# sensorbridge.net
KiCad netlist of a schematic drawn in EAGLE
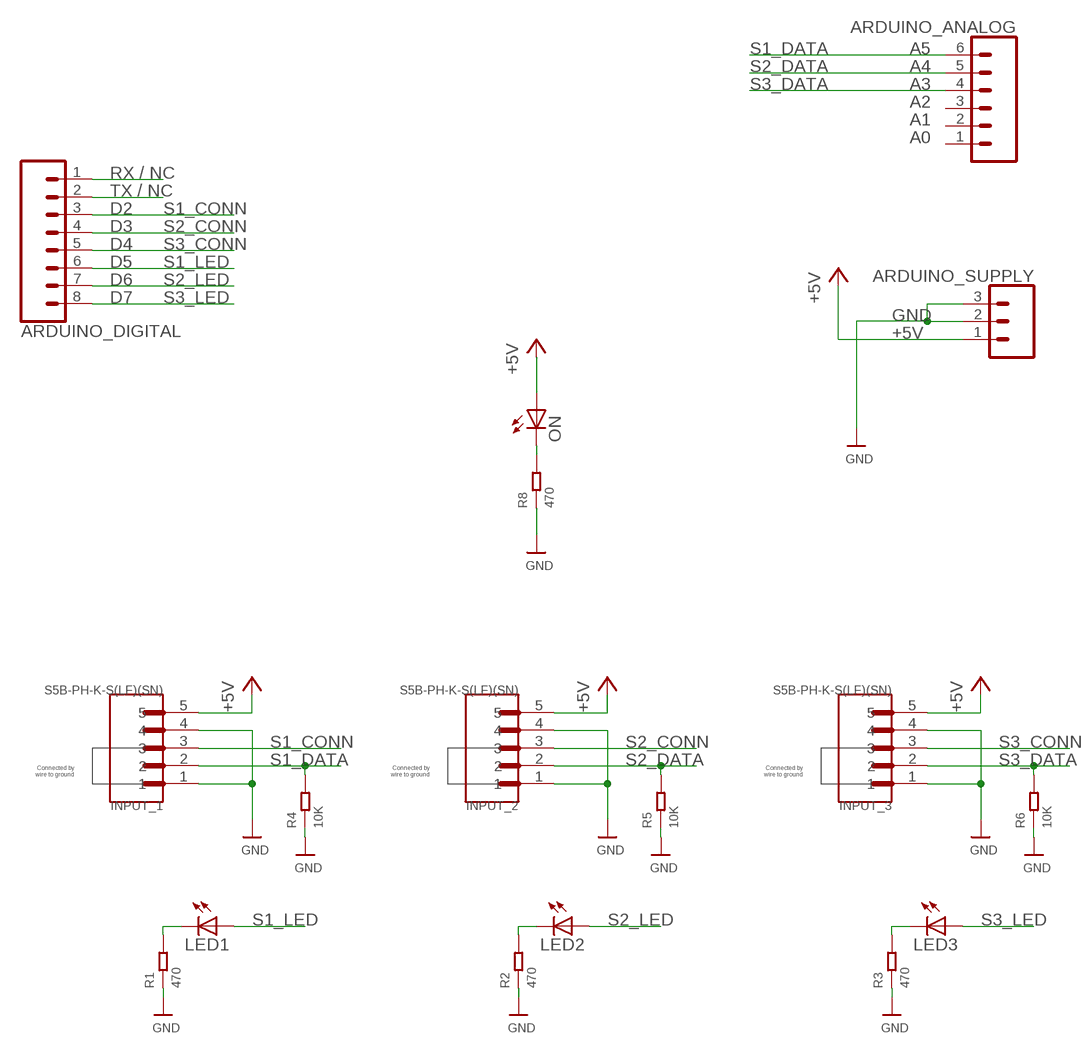
[diagram p0: schematic, sheet 1]

(export (version "E")
  (design (tool "Eeschema 10.0.6"))
  (components
    (comp (ref "ARDUINO_ANALOG")
      (value "CONN_06NO_SILK_FEMALE_PTH")
      (footprint "eagle-import:1X06_NO_SILK")
      (libsource (lib "eagle-import") (part "CONN_06NO_SILK_FEMALE_PTH"))
    )
    (comp (ref "ARDUINO_DIGITAL")
      (value "CONN_08NO_SILK_FEMALE_PTH")
      (footprint "eagle-import:1X08_NO_SILK")
      (libsource (lib "eagle-import") (part "CONN_08NO_SILK_FEMALE_PTH"))
    )
    (comp (ref "ARDUINO_SUPPLY")
      (value "CONN_031X03_NO_SILK")
      (footprint "eagle-import:1X03_NO_SILK")
      (libsource (lib "eagle-import") (part "CONN_031X03_NO_SILK"))
    )
    (comp (ref "INPUT_1")
      (value "S5B-PH-K-S(LF)(SN)")
      (footprint "eagle-import:JST_S5B-PH-K-S(LF)(SN)")
      (fields (field (name "MF") "JST"))
      (libsource (lib "eagle-import") (part "S5B-PH-K-S(LF)(SN)"))
    )
    (comp (ref "INPUT_2")
      (value "S5B-PH-K-S(LF)(SN)")
      (footprint "eagle-import:JST_S5B-PH-K-S(LF)(SN)")
      (fields (field (name "MF") "JST"))
      (libsource (lib "eagle-import") (part "S5B-PH-K-S(LF)(SN)"))
    )
    (comp (ref "INPUT_3")
      (value "S5B-PH-K-S(LF)(SN)")
      (footprint "eagle-import:JST_S5B-PH-K-S(LF)(SN)")
      (fields (field (name "MF") "JST"))
      (libsource (lib "eagle-import") (part "S5B-PH-K-S(LF)(SN)"))
    )
    (comp (ref "LED1")
      (value "LEDCHIP-LED0603")
      (footprint "eagle-import:CHIP-LED0603")
      (libsource (lib "eagle-import") (part "LEDCHIP-LED0603"))
    )
    (comp (ref "LED2")
      (value "LEDCHIP-LED0603")
      (footprint "eagle-import:CHIP-LED0603")
      (libsource (lib "eagle-import") (part "LEDCHIP-LED0603"))
    )
    (comp (ref "LED3")
      (value "LEDCHIP-LED0603")
      (footprint "eagle-import:CHIP-LED0603")
      (libsource (lib "eagle-import") (part "LEDCHIP-LED0603"))
    )
    (comp (ref "ON")
      (value "LEDCHIP-LED0603")
      (footprint "eagle-import:CHIP-LED0603")
      (libsource (lib "eagle-import") (part "LEDCHIP-LED0603"))
    )
    (comp (ref "R1")
      (value "470")
      (footprint "eagle-import:R0603")
      (libsource (lib "eagle-import") (part "RES-0603"))
    )
    (comp (ref "R2")
      (value "470")
      (footprint "eagle-import:R0603")
      (libsource (lib "eagle-import") (part "RES-0603"))
    )
    (comp (ref "R3")
      (value "470")
      (footprint "eagle-import:R0603")
      (libsource (lib "eagle-import") (part "RES-0603"))
    )
    (comp (ref "R4")
      (value "10K")
      (footprint "eagle-import:R0603")
      (libsource (lib "eagle-import") (part "RES-0603"))
    )
    (comp (ref "R5")
      (value "10K")
      (footprint "eagle-import:R0603")
      (libsource (lib "eagle-import") (part "RES-0603"))
    )
    (comp (ref "R6")
      (value "10K")
      (footprint "eagle-import:R0603")
      (libsource (lib "eagle-import") (part "RES-0603"))
    )
    (comp (ref "R8")
      (value "470")
      (footprint "eagle-import:R0603")
      (libsource (lib "eagle-import") (part "RES-0603"))
    )
  )
  (nets
    (net (code "1") (name "+5V") (class "Default")
      (node (ref "ARDUINO_SUPPLY") (pin "1") (pinfunction "1_1") (pintype "passive"))
      (node (ref "INPUT_1") (pin "5") (pinfunction "5_5") (pintype "passive"))
      (node (ref "INPUT_2") (pin "5") (pinfunction "5_5") (pintype "passive"))
      (node (ref "INPUT_3") (pin "5") (pinfunction "5_5") (pintype "passive"))
      (node (ref "ON") (pin "A") (pinfunction "A_A") (pintype "passive"))
    )
    (net (code "2") (name "/S1_CONN") (class "Default")
      (node (ref "ARDUINO_DIGITAL") (pin "3") (pinfunction "3_3") (pintype "passive"))
      (node (ref "INPUT_1") (pin "3") (pinfunction "3_3") (pintype "passive"))
    )
    (net (code "3") (name "/S1_DATA") (class "Default")
      (node (ref "ARDUINO_ANALOG") (pin "6") (pinfunction "6_6") (pintype "passive"))
      (node (ref "INPUT_1") (pin "2") (pinfunction "2_2") (pintype "passive"))
      (node (ref "R4") (pin "2") (pinfunction "2_2") (pintype "passive"))
    )
    (net (code "4") (name "/S1_LED") (class "Default")
      (node (ref "ARDUINO_DIGITAL") (pin "6") (pinfunction "6_6") (pintype "passive"))
      (node (ref "LED1") (pin "A") (pinfunction "A_A") (pintype "passive"))
    )
    (net (code "5") (name "/S2_CONN") (class "Default")
      (node (ref "ARDUINO_DIGITAL") (pin "4") (pinfunction "4_4") (pintype "passive"))
      (node (ref "INPUT_2") (pin "3") (pinfunction "3_3") (pintype "passive"))
    )
    (net (code "6") (name "/S2_DATA") (class "Default")
      (node (ref "ARDUINO_ANALOG") (pin "5") (pinfunction "5_5") (pintype "passive"))
      (node (ref "INPUT_2") (pin "2") (pinfunction "2_2") (pintype "passive"))
      (node (ref "R5") (pin "2") (pinfunction "2_2") (pintype "passive"))
    )
    (net (code "7") (name "/S2_LED") (class "Default")
      (node (ref "ARDUINO_DIGITAL") (pin "7") (pinfunction "7_7") (pintype "passive"))
      (node (ref "LED2") (pin "A") (pinfunction "A_A") (pintype "passive"))
    )
    (net (code "8") (name "/S3_CONN") (class "Default")
      (node (ref "ARDUINO_DIGITAL") (pin "5") (pinfunction "5_5") (pintype "passive"))
      (node (ref "INPUT_3") (pin "3") (pinfunction "3_3") (pintype "passive"))
    )
    (net (code "9") (name "/S3_DATA") (class "Default")
      (node (ref "ARDUINO_ANALOG") (pin "4") (pinfunction "4_4") (pintype "passive"))
      (node (ref "INPUT_3") (pin "2") (pinfunction "2_2") (pintype "passive"))
      (node (ref "R6") (pin "2") (pinfunction "2_2") (pintype "passive"))
    )
    (net (code "10") (name "/S3_LED") (class "Default")
      (node (ref "ARDUINO_DIGITAL") (pin "8") (pinfunction "8_8") (pintype "passive"))
      (node (ref "LED3") (pin "A") (pinfunction "A_A") (pintype "passive"))
    )
    (net (code "11") (name "GND") (class "Default")
      (node (ref "ARDUINO_SUPPLY") (pin "2") (pinfunction "2_2") (pintype "passive"))
      (node (ref "ARDUINO_SUPPLY") (pin "3") (pinfunction "3_3") (pintype "passive"))
      (node (ref "INPUT_1") (pin "1") (pinfunction "1_1") (pintype "passive"))
      (node (ref "INPUT_1") (pin "4") (pinfunction "4_4") (pintype "passive"))
      (node (ref "INPUT_2") (pin "1") (pinfunction "1_1") (pintype "passive"))
      (node (ref "INPUT_2") (pin "4") (pinfunction "4_4") (pintype "passive"))
      (node (ref "INPUT_3") (pin "1") (pinfunction "1_1") (pintype "passive"))
      (node (ref "INPUT_3") (pin "4") (pinfunction "4_4") (pintype "passive"))
      (node (ref "R1") (pin "1") (pinfunction "1_1") (pintype "passive"))
      (node (ref "R2") (pin "1") (pinfunction "1_1") (pintype "passive"))
      (node (ref "R3") (pin "1") (pinfunction "1_1") (pintype "passive"))
      (node (ref "R4") (pin "1") (pinfunction "1_1") (pintype "passive"))
      (node (ref "R5") (pin "1") (pinfunction "1_1") (pintype "passive"))
      (node (ref "R6") (pin "1") (pinfunction "1_1") (pintype "passive"))
      (node (ref "R8") (pin "1") (pinfunction "1_1") (pintype "passive"))
    )
    (net (code "12") (name "Net-(LED1-PadC)") (class "Default")
      (node (ref "LED1") (pin "C") (pinfunction "C_C") (pintype "passive"))
      (node (ref "R1") (pin "2") (pinfunction "2_2") (pintype "passive"))
    )
    (net (code "13") (name "Net-(LED2-PadC)") (class "Default")
      (node (ref "LED2") (pin "C") (pinfunction "C_C") (pintype "passive"))
      (node (ref "R2") (pin "2") (pinfunction "2_2") (pintype "passive"))
    )
    (net (code "14") (name "Net-(LED3-PadC)") (class "Default")
      (node (ref "LED3") (pin "C") (pinfunction "C_C") (pintype "passive"))
      (node (ref "R3") (pin "2") (pinfunction "2_2") (pintype "passive"))
    )
    (net (code "15") (name "Net-(ON-PadC)") (class "Default")
      (node (ref "ON") (pin "C") (pinfunction "C_C") (pintype "passive"))
      (node (ref "R8") (pin "2") (pinfunction "2_2") (pintype "passive"))
    )
    (net (code "16") (name "unconnected-(ARDUINO_ANALOG-Pad1)") (class "Default")
      (node (ref "ARDUINO_ANALOG") (pin "1") (pinfunction "1_1") (pintype "passive"))
    )
    (net (code "17") (name "unconnected-(ARDUINO_ANALOG-Pad2)") (class "Default")
      (node (ref "ARDUINO_ANALOG") (pin "2") (pinfunction "2_2") (pintype "passive"))
    )
    (net (code "18") (name "unconnected-(ARDUINO_ANALOG-Pad3)") (class "Default")
      (node (ref "ARDUINO_ANALOG") (pin "3") (pinfunction "3_3") (pintype "passive"))
    )
    (net (code "19") (name "unconnected-(ARDUINO_DIGITAL-Pad1)") (class "Default")
      (node (ref "ARDUINO_DIGITAL") (pin "1") (pinfunction "1_1") (pintype "passive"))
    )
    (net (code "20") (name "unconnected-(ARDUINO_DIGITAL-Pad2)") (class "Default")
      (node (ref "ARDUINO_DIGITAL") (pin "2") (pinfunction "2_2") (pintype "passive"))
    )
  )
)
